# HRT1.net
KiCad netlist of a schematic drawn in Altium Designer
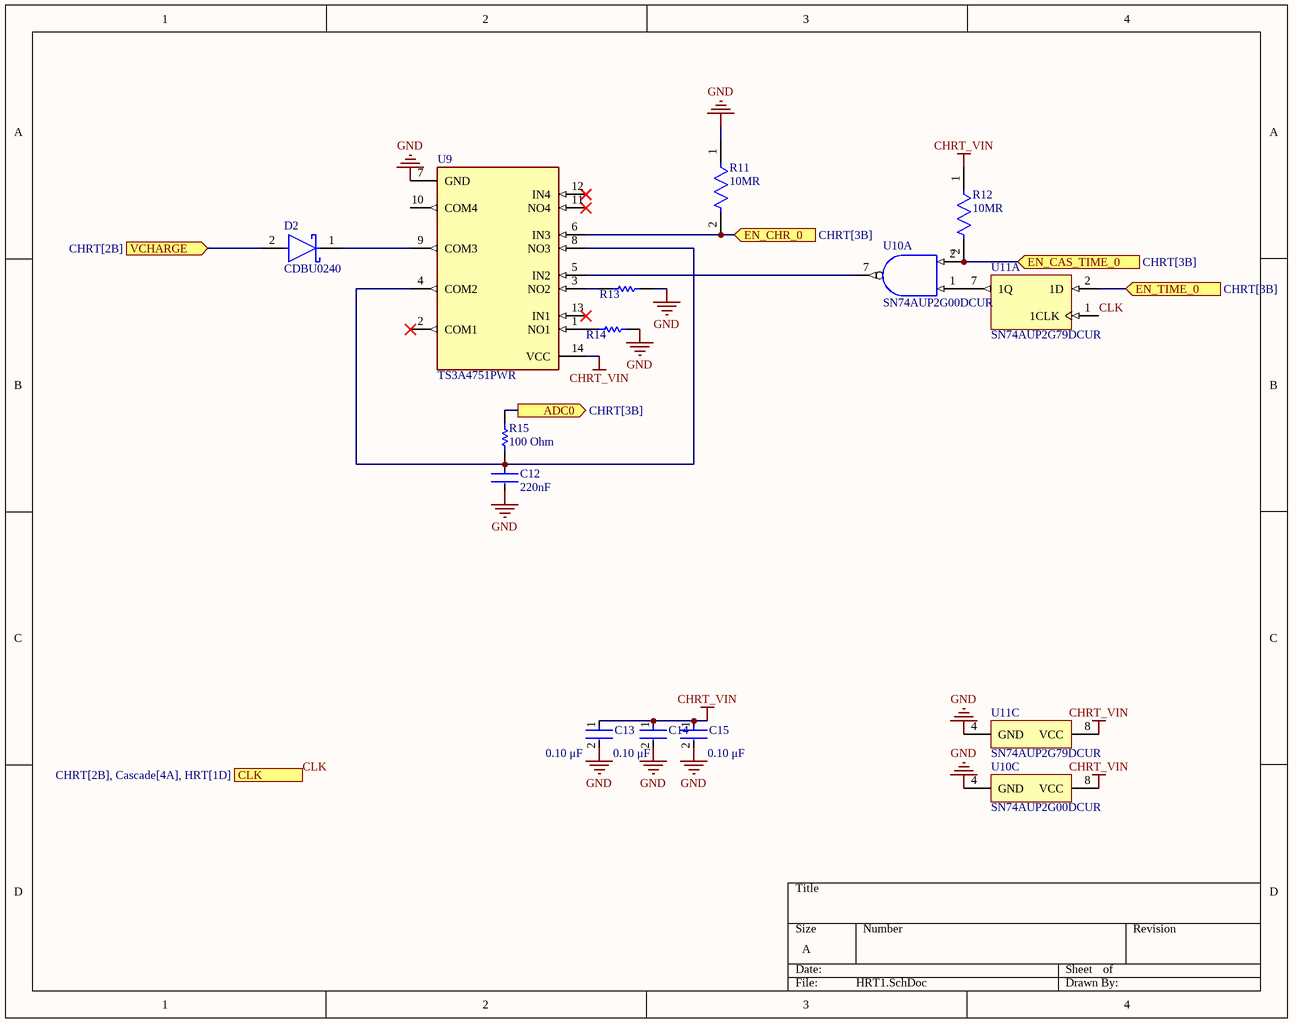
[diagram p0: HRT1.SchDoc]

(export (version "E")
  (design (tool "Eeschema 10.0.6"))
  (components
    (comp (ref "C12")
      (value "GRM155R71C224KA12D")
      (footprint "FP-GRM155-0_05-IPC_C")
      (description "Chip Multilayer Ceramic Capacitors for General Purpose, 0402, 0.22uF, X7R, 15%, 10%, 16V")
      (fields
        (field (name "CAPACITANCE") "220nF")
        (field (name "VOLTAGE") "16V")
        (field (name "TOLERANCE") "10%")
      )
      (libsource (lib "Altium Content Vault") (part "02cd4be3c70576c341d710602a673aa"))
    )
    (comp (ref "C13")
      (value "C0402C104K8PACTU")
      (footprint "FP-C0402-BB-MFG")
      (description "CAP CER 0.1UF 10V X5R 0402")
      (fields
        (field (name "CAPACITANCE") "0.10 μF")
        (field (name "MANUFACTURER") "Kemet")
        (field (name "TOLERANCE") "0.1")
      )
      (libsource (lib "Altium Content Vault") (part "b4654b650e69147ec39a6b967a45e02"))
    )
    (comp (ref "C14")
      (value "C0402C104K8PACTU")
      (footprint "FP-C0402-BB-MFG")
      (description "CAP CER 0.1UF 10V X5R 0402")
      (fields
        (field (name "CAPACITANCE") "0.10 μF")
        (field (name "MANUFACTURER") "Kemet")
        (field (name "TOLERANCE") "0.1")
      )
      (libsource (lib "Altium Content Vault") (part "b4654b650e69147ec39a6b967a45e02"))
    )
    (comp (ref "C15")
      (value "C0402C104K8PACTU")
      (footprint "FP-C0402-BB-MFG")
      (description "CAP CER 0.1UF 10V X5R 0402")
      (fields
        (field (name "CAPACITANCE") "0.10 μF")
        (field (name "MANUFACTURER") "Kemet")
        (field (name "TOLERANCE") "0.1")
      )
      (libsource (lib "Altium Content Vault") (part "b4654b650e69147ec39a6b967a45e02"))
    )
    (comp (ref "D2")
      (value "CDBU0240")
      (footprint "FP-SOD-523F-MFG")
      (description "DIODE SCHOTTKY 40V 200MA 0603")
      (libsource (lib "Altium Content Vault") (part "1d6ec82d83fb6aee721767c19dac4b9"))
    )
    (comp (ref "R11")
      (value "CRCW040210M0JNED")
      (footprint "FP-CRCW0402-e3-IPC_C")
      (description "RES Thick Film, 10MΩ, 5%, 0.063W, 200ppm/°C, 0402")
      (fields (field (name "TOLERANCE") "5%") (field (name "RESISTANCE") "10MR"))
      (libsource (lib "Altium Content Vault") (part "1029c3af85768c4190bb7ad29bc67b5"))
    )
    (comp (ref "R12")
      (value "CRCW040210M0JNED")
      (footprint "FP-CRCW0402-e3-IPC_C")
      (description "RES Thick Film, 10MΩ, 5%, 0.063W, 200ppm/°C, 0402")
      (fields (field (name "TOLERANCE") "5%") (field (name "RESISTANCE") "10MR"))
      (libsource (lib "Altium Content Vault") (part "1029c3af85768c4190bb7ad29bc67b5"))
    )
    (comp (ref "R13")
      (value "CRCW040222R0FKED")
      (footprint "RESC1005X40X25LL05T05")
      (fields (field (name "MANUFACTURER") "Vishay Dale"))
      (libsource (lib "Altium Content Vault") (part "RES"))
    )
    (comp (ref "R14")
      (value "CRCW040222R0FKED")
      (footprint "RESC1005X40X25LL05T05")
      (fields (field (name "MANUFACTURER") "Vishay Dale"))
      (libsource (lib "Altium Content Vault") (part "RES"))
    )
    (comp (ref "R15")
      (value "ERJ-2RKF1000X")
      (footprint "RESC1005X40X25LL05T05")
      (description "Chip Resistor, 100 Ohm, +/- 1%, 100 mW, -55 to 155 degC, 0402 (1005 Metric), RoHS, Tape and Reel")
      (fields
        (field (name "MANUFACTURER") "Basic Passives")
        (field (name "TOLERANCE") "1%")
        (field (name "RESISTANCE") "100 Ohm")
      )
      (libsource (lib "Altium Content Vault") (part "RES-2"))
    )
    (comp (ref "U9")
      (value "TS3A4751PWR")
      (footprint "FP-PW0014A-IPC_C")
      (description "IC SWITCH QUAD SPST 14TSSOP")
      (libsource (lib "Altium Content Vault") (part "75fdcfb842d41a92b92a478e82e68ae"))
    )
    (comp (ref "U10")
      (value "SN74AUP2G00DCUR")
      (footprint "DCU0008A_L")
      (description "Low-Power Dual 2-Input Positive-NAND Gate, DCU0008A, LARGE T&R")
      (fields
        (field (name "GENERIC PART NUMBER") "SN74AUP2G00")
        (field (name "MANUFACTURER") "Texas Instruments")
      )
      (libsource (lib "Altium Content Vault") (part "TI-SN74XXX2GXXX-8"))
    )
    (comp (ref "U11")
      (value "SN74AUP2G79DCUR")
      (footprint "DCU0008A_L")
      (description "Low-Power Dual Positive-Edge-Triggered D-Type Flip-Flop, DCU0008A, LARGE T&R")
      (fields
        (field (name "MANUFACTURER") "Texas Instruments")
        (field (name "GENERIC PART NUMBER") "SN74AUP2G79")
      )
      (libsource (lib "Altium Content Vault") (part "TI-SN74XXX2G79-8_A"))
    )
  )
  (nets
    (net (code "1") (name "/ADC0") (class "Default")
      (node (ref "R15") (pin "2") (pinfunction "2_2") (pintype "passive"))
    )
    (net (code "2") (name "/CLK") (class "Default")
      (node (ref "U11") (pin "1") (pinfunction "1CLK_1") (pintype "input"))
    )
    (net (code "3") (name "/EN_CAS_TIME_0") (class "Default")
      (node (ref "R12") (pin "2") (pinfunction "2_2") (pintype "passive"))
      (node (ref "U10") (pin "2") (pinfunction "1B_2") (pintype "input"))
    )
    (net (code "4") (name "/EN_CHR_0") (class "Default")
      (node (ref "R11") (pin "2") (pinfunction "2_2") (pintype "passive"))
      (node (ref "U9") (pin "6") (pinfunction "IN3_6") (pintype "input"))
    )
    (net (code "5") (name "/EN_TIME_0") (class "Default")
      (node (ref "U11") (pin "2") (pinfunction "1D_2") (pintype "input"))
    )
    (net (code "6") (name "/VCHARGE") (class "Default")
      (node (ref "D2") (pin "2") (pinfunction "A_2") (pintype "passive"))
    )
    (net (code "7") (name "CHRT_VIN") (class "Default")
      (node (ref "C13") (pin "1") (pinfunction "1_1") (pintype "passive"))
      (node (ref "C14") (pin "1") (pinfunction "1_1") (pintype "passive"))
      (node (ref "C15") (pin "1") (pinfunction "1_1") (pintype "passive"))
      (node (ref "R12") (pin "1") (pinfunction "1_1") (pintype "passive"))
      (node (ref "U10") (pin "8") (pinfunction "VCC_8") (pintype "power_in"))
      (node (ref "U11") (pin "8") (pinfunction "VCC_8") (pintype "power_in"))
      (node (ref "U9") (pin "14") (pinfunction "VCC_14") (pintype "power_in"))
    )
    (net (code "8") (name "GND") (class "Default")
      (node (ref "C12") (pin "2") (pinfunction "2_2") (pintype "passive"))
      (node (ref "C13") (pin "2") (pinfunction "2_2") (pintype "passive"))
      (node (ref "C14") (pin "2") (pinfunction "2_2") (pintype "passive"))
      (node (ref "C15") (pin "2") (pinfunction "2_2") (pintype "passive"))
      (node (ref "R11") (pin "1") (pinfunction "1_1") (pintype "passive"))
      (node (ref "R13") (pin "2") (pinfunction "2_2") (pintype "passive"))
      (node (ref "R14") (pin "2") (pinfunction "2_2") (pintype "passive"))
      (node (ref "U10") (pin "4") (pinfunction "GND_4") (pintype "power_in"))
      (node (ref "U11") (pin "4") (pinfunction "GND_4") (pintype "power_in"))
      (node (ref "U9") (pin "7") (pinfunction "GND_7") (pintype "power_in"))
    )
    (net (code "9") (name "Net-(D2-C)") (class "Default")
      (node (ref "D2") (pin "1") (pinfunction "C_1") (pintype "passive"))
      (node (ref "U9") (pin "9") (pinfunction "COM3_9") (pintype "output"))
    )
    (net (code "10") (name "Net-(U9-COM2)") (class "Default")
      (node (ref "C12") (pin "1") (pinfunction "1_1") (pintype "passive"))
      (node (ref "R15") (pin "1") (pinfunction "1_1") (pintype "passive"))
      (node (ref "U9") (pin "4") (pinfunction "COM2_4") (pintype "output"))
      (node (ref "U9") (pin "8") (pinfunction "NO3_8") (pintype "input"))
    )
    (net (code "11") (name "Net-(U9-NO1)") (class "Default")
      (node (ref "R14") (pin "1") (pinfunction "1_1") (pintype "passive"))
      (node (ref "U9") (pin "1") (pinfunction "NO1_1") (pintype "input"))
    )
    (net (code "12") (name "Net-(U9-NO2)") (class "Default")
      (node (ref "R13") (pin "1") (pinfunction "1_1") (pintype "passive"))
      (node (ref "U9") (pin "3") (pinfunction "NO2_3") (pintype "input"))
    )
    (net (code "13") (name "Net-(U10A-1A)") (class "Default")
      (node (ref "U10") (pin "1") (pinfunction "1A_1") (pintype "input"))
      (node (ref "U11") (pin "7") (pinfunction "1Q_7") (pintype "output"))
    )
    (net (code "14") (name "Net-(U10A-1Y)") (class "Default")
      (node (ref "U10") (pin "7") (pinfunction "1Y_7") (pintype "output"))
      (node (ref "U9") (pin "5") (pinfunction "IN2_5") (pintype "input"))
    )
    (net (code "15") (name "unconnected-(U9-COM1-Pad2)") (class "Default")
      (node (ref "U9") (pin "2") (pinfunction "COM1_2") (pintype "output+no_connect"))
    )
    (net (code "16") (name "unconnected-(U9-COM4-Pad10)") (class "Default")
      (node (ref "U9") (pin "10") (pinfunction "COM4_10") (pintype "output"))
    )
    (net (code "17") (name "unconnected-(U9-IN1-Pad13)") (class "Default")
      (node (ref "U9") (pin "13") (pinfunction "IN1_13") (pintype "input+no_connect"))
    )
    (net (code "18") (name "unconnected-(U9-IN4-Pad12)") (class "Default")
      (node (ref "U9") (pin "12") (pinfunction "IN4_12") (pintype "input+no_connect"))
    )
    (net (code "19") (name "unconnected-(U9-NO4-Pad11)") (class "Default")
      (node (ref "U9") (pin "11") (pinfunction "NO4_11") (pintype "input+no_connect"))
    )
  )
)
